# cpu1_gsm_comm.net
KiCad netlist of a schematic drawn in Altium Designer
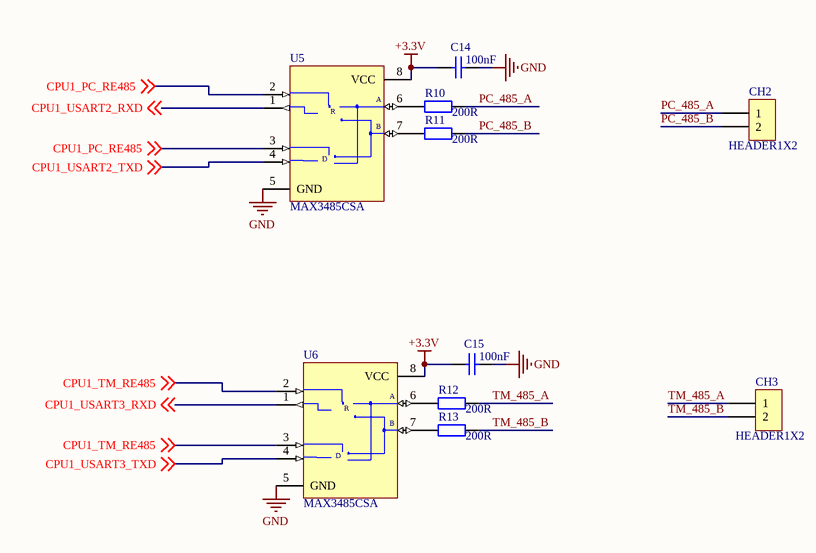
[diagram p0: cpu1_gsm_comm.SchDoc]

(export (version "E")
  (design (tool "Eeschema 10.0.6"))
  (components
    (comp (ref "C14")
      (value "100nF")
      (footprint "0805_C")
      (description "贴片电容")
      (libsource (lib "Miscellaneous Devices LC") (part "0805 100nF(104) 10% 50V"))
    )
    (comp (ref "C15")
      (value "100nF")
      (footprint "0805_C")
      (description "贴片电容")
      (libsource (lib "Miscellaneous Devices LC") (part "0805 100nF(104) 10% 50V"))
    )
    (comp (ref "CH2")
      (value "HEADER1X2")
      (footprint "CH3.96-2PIN")
      (libsource (lib "myIntegrated_Library1") (part "HEADER1X2"))
    )
    (comp (ref "CH3")
      (value "HEADER1X2")
      (footprint "CH3.96-2PIN")
      (libsource (lib "myIntegrated_Library1") (part "HEADER1X2"))
    )
    (comp (ref "R10")
      (value "200R")
      (footprint "0805_R")
      (description "贴片电阻")
      (libsource (lib "Miscellaneous Devices LC") (part "0805 11KΩ (1102) 1%"))
    )
    (comp (ref "R11")
      (value "200R")
      (footprint "0805_R")
      (description "贴片电阻")
      (libsource (lib "Miscellaneous Devices LC") (part "0805 11KΩ (1102) 1%"))
    )
    (comp (ref "R12")
      (value "200R")
      (footprint "0805_R")
      (description "贴片电阻")
      (libsource (lib "Miscellaneous Devices LC") (part "0805 11KΩ (1102) 1%"))
    )
    (comp (ref "R13")
      (value "200R")
      (footprint "0805_R")
      (description "贴片电阻")
      (libsource (lib "Miscellaneous Devices LC") (part "0805 11KΩ (1102) 1%"))
    )
    (comp (ref "U5")
      (value "MAX3485CSA")
      (footprint "NS08-L")
      (libsource (lib "myIntegrated_Library1") (part "MAX485CSA"))
    )
    (comp (ref "U6")
      (value "MAX3485CSA")
      (footprint "NS08-L")
      (libsource (lib "myIntegrated_Library1") (part "MAX485CSA"))
    )
  )
  (nets
    (net (code "1") (name "+3.3V") (class "Default")
      (node (ref "C14") (pin "2") (pinfunction "2_2") (pintype "passive"))
      (node (ref "C15") (pin "2") (pinfunction "2_2") (pintype "passive"))
      (node (ref "U5") (pin "8") (pinfunction "VCC_8") (pintype "power_in"))
      (node (ref "U6") (pin "8") (pinfunction "VCC_8") (pintype "power_in"))
    )
    (net (code "2") (name "/PC_485_A") (class "Default")
      (node (ref "CH2") (pin "1") (pinfunction "1_1") (pintype "passive"))
      (node (ref "R10") (pin "2") (pinfunction "2_2") (pintype "passive"))
    )
    (net (code "3") (name "/PC_485_B") (class "Default")
      (node (ref "CH2") (pin "2") (pinfunction "2_2") (pintype "passive"))
      (node (ref "R11") (pin "2") (pinfunction "2_2") (pintype "passive"))
    )
    (net (code "4") (name "/TM_485_A") (class "Default")
      (node (ref "CH3") (pin "1") (pinfunction "1_1") (pintype "passive"))
      (node (ref "R12") (pin "2") (pinfunction "2_2") (pintype "passive"))
    )
    (net (code "5") (name "/TM_485_B") (class "Default")
      (node (ref "CH3") (pin "2") (pinfunction "2_2") (pintype "passive"))
      (node (ref "R13") (pin "2") (pinfunction "2_2") (pintype "passive"))
    )
    (net (code "6") (name "CPU1_PC_RE485") (class "Default")
      (node (ref "U5") (pin "2") (pinfunction "~{RE}_2") (pintype "input"))
      (node (ref "U5") (pin "3") (pinfunction "DE_3") (pintype "input"))
    )
    (net (code "7") (name "CPU1_TM_RE485") (class "Default")
      (node (ref "U6") (pin "2") (pinfunction "~{RE}_2") (pintype "input"))
      (node (ref "U6") (pin "3") (pinfunction "DE_3") (pintype "input"))
    )
    (net (code "8") (name "CPU1_USART2_RXD") (class "Default")
      (node (ref "U5") (pin "1") (pinfunction "RO_1") (pintype "output"))
    )
    (net (code "9") (name "CPU1_USART2_TXD") (class "Default")
      (node (ref "U5") (pin "4") (pinfunction "DI_4") (pintype "input"))
    )
    (net (code "10") (name "CPU1_USART3_RXD") (class "Default")
      (node (ref "U6") (pin "1") (pinfunction "RO_1") (pintype "output"))
    )
    (net (code "11") (name "CPU1_USART3_TXD") (class "Default")
      (node (ref "U6") (pin "4") (pinfunction "DI_4") (pintype "input"))
    )
    (net (code "12") (name "GND") (class "Default")
      (node (ref "C14") (pin "1") (pinfunction "1_1") (pintype "passive"))
      (node (ref "C15") (pin "1") (pinfunction "1_1") (pintype "passive"))
      (node (ref "U5") (pin "5") (pinfunction "GND_5") (pintype "power_in"))
      (node (ref "U6") (pin "5") (pinfunction "GND_5") (pintype "power_in"))
    )
    (net (code "13") (name "Net-(U5-A)") (class "Default")
      (node (ref "R10") (pin "1") (pinfunction "1_1") (pintype "passive"))
      (node (ref "U5") (pin "6") (pinfunction "A_6") (pintype "bidirectional"))
    )
    (net (code "14") (name "Net-(U5-B)") (class "Default")
      (node (ref "R11") (pin "1") (pinfunction "1_1") (pintype "passive"))
      (node (ref "U5") (pin "7") (pinfunction "B_7") (pintype "bidirectional"))
    )
    (net (code "15") (name "Net-(U6-A)") (class "Default")
      (node (ref "R12") (pin "1") (pinfunction "1_1") (pintype "passive"))
      (node (ref "U6") (pin "6") (pinfunction "A_6") (pintype "bidirectional"))
    )
    (net (code "16") (name "Net-(U6-B)") (class "Default")
      (node (ref "R13") (pin "1") (pinfunction "1_1") (pintype "passive"))
      (node (ref "U6") (pin "7") (pinfunction "B_7") (pintype "bidirectional"))
    )
  )
)
